# RTI-Dome-wire.net
KiCad netlist of a schematic drawn in EAGLE
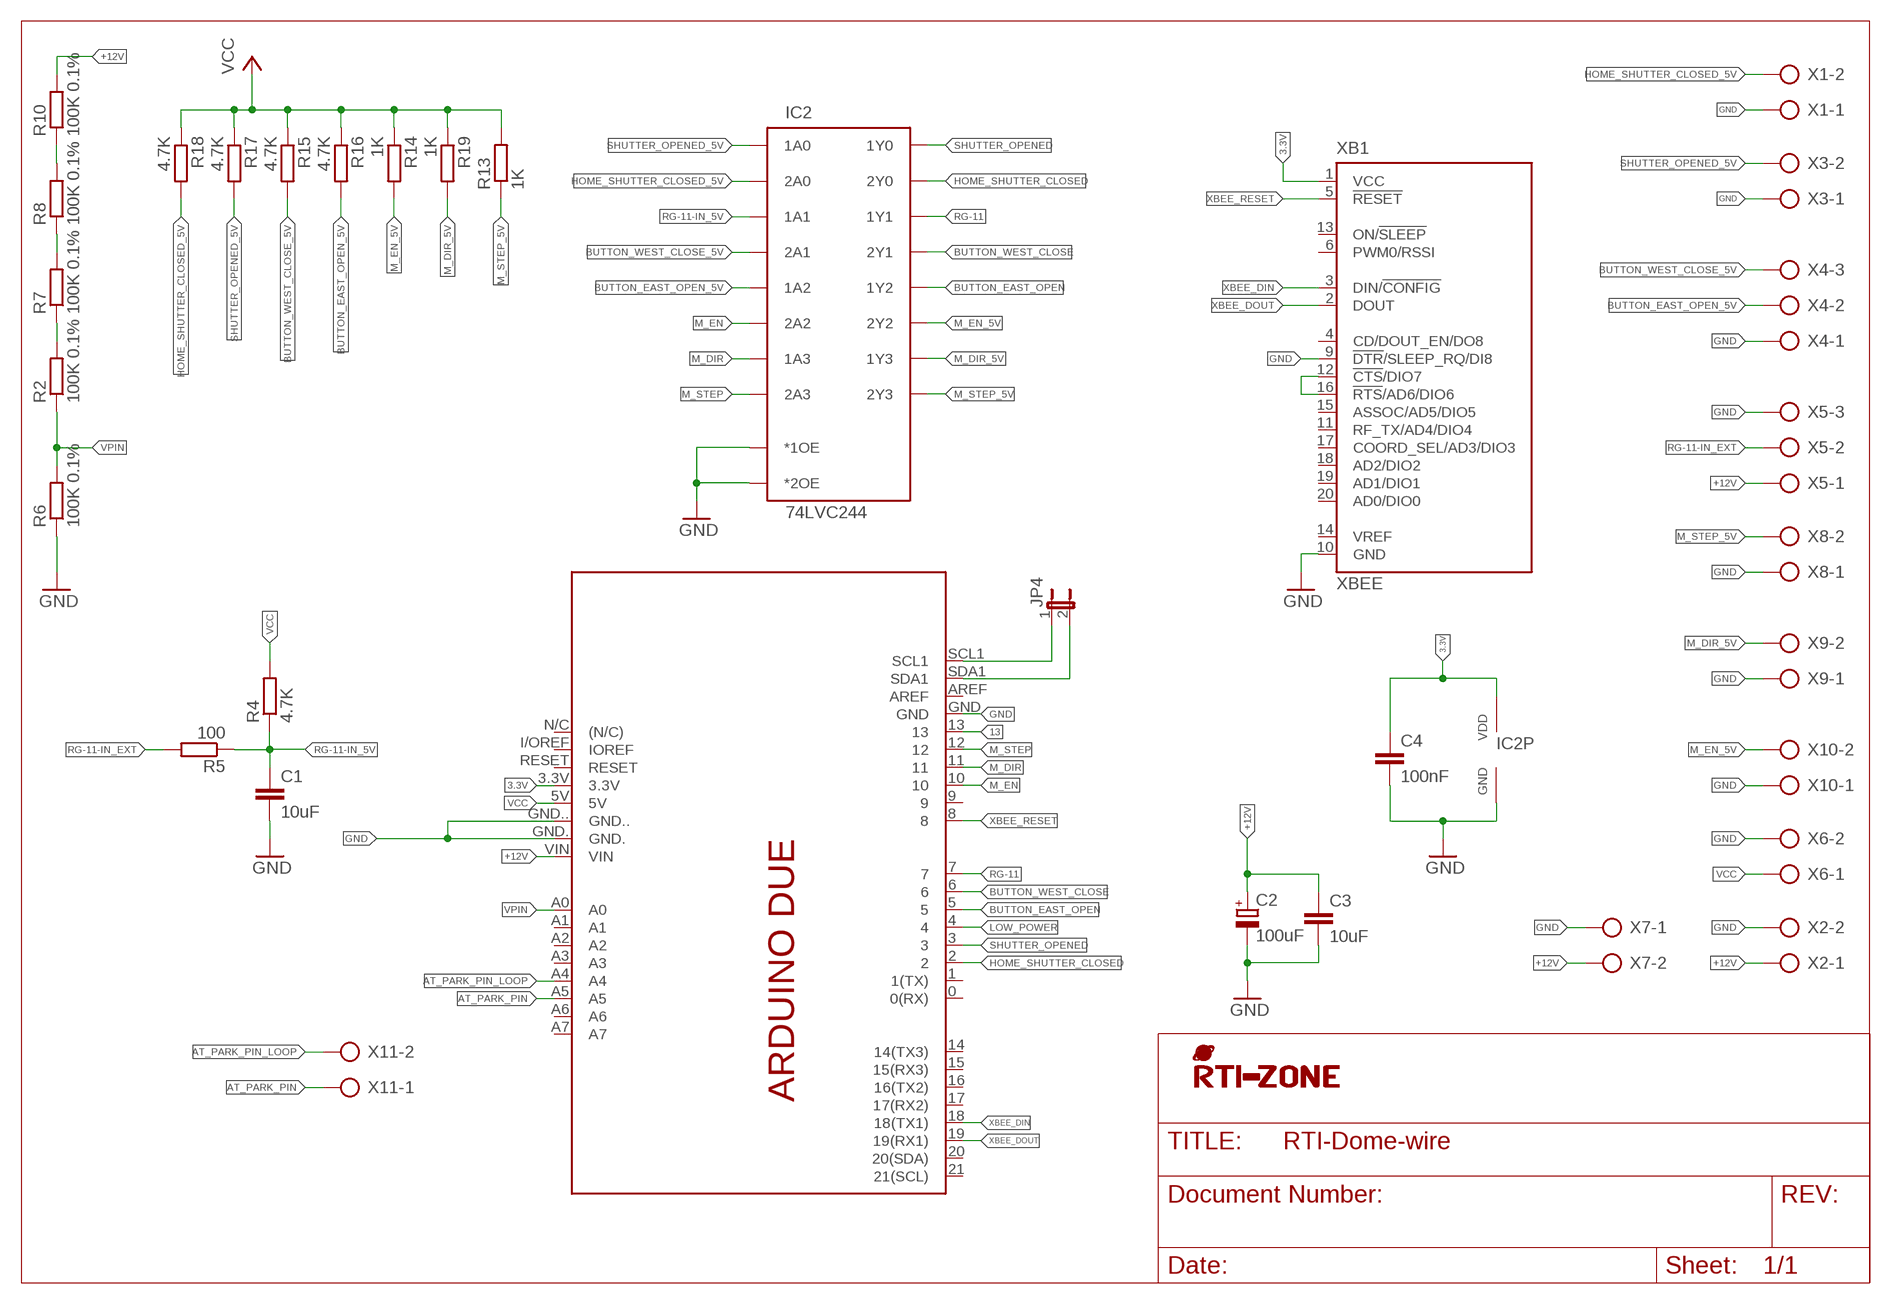
[diagram p0: schematic, sheet 1]

(export (version "E")
  (design (tool "Eeschema 10.0.6"))
  (components
    (comp (ref "C1")
      (value "10uF")
      (footprint "eagle-import:C0805")
      (libsource (lib "eagle-import") (part "C-EU'0805'"))
    )
    (comp (ref "C2")
      (value "100uF")
      (footprint "eagle-import:UD-10X10_NICHICON")
      (libsource (lib "eagle-import") (part "CPOL-EU"))
    )
    (comp (ref "C3")
      (value "10uF")
      (footprint "eagle-import:C0805")
      (libsource (lib "eagle-import") (part "C-EU'0805'"))
    )
    (comp (ref "C4")
      (value "100nF")
      (footprint "eagle-import:C0805")
      (libsource (lib "eagle-import") (part "C-EU'0805'"))
    )
    (comp (ref "IC2")
      (value "74LVC244")
      (footprint "eagle-import:TSSOP20")
      (libsource (lib "eagle-import") (part "74244LVC"))
    )
    (comp (ref "JP4")
      (value "JP1E")
      (footprint "eagle-import:JP1")
      (libsource (lib "eagle-import") (part "JP1E"))
    )
    (comp (ref "PCB1")
      (value "ARDUINO_DUE_SHIELD_SHORT")
      (footprint "eagle-import:ARDUINO_DUE_SHIELD_SHORT")
      (libsource (lib "eagle-import") (part "ARDUINO_DUE_SHIELD_SHORT"))
    )
    (comp (ref "R2")
      (value "100K 0.1%")
      (footprint "eagle-import:R0805")
      (libsource (lib "eagle-import") (part "R-EU'0805'"))
    )
    (comp (ref "R4")
      (value "4.7K")
      (footprint "eagle-import:R0805")
      (libsource (lib "eagle-import") (part "R-EU'0805'"))
    )
    (comp (ref "R5")
      (value "100")
      (footprint "eagle-import:R0805")
      (libsource (lib "eagle-import") (part "R-EU'0805'"))
    )
    (comp (ref "R6")
      (value "100K 0.1%")
      (footprint "eagle-import:R0805")
      (libsource (lib "eagle-import") (part "R-EU'0805'"))
    )
    (comp (ref "R7")
      (value "100K 0.1%")
      (footprint "eagle-import:R0805")
      (libsource (lib "eagle-import") (part "R-EU'0805'"))
    )
    (comp (ref "R8")
      (value "100K 0.1%")
      (footprint "eagle-import:R0805")
      (libsource (lib "eagle-import") (part "R-EU'0805'"))
    )
    (comp (ref "R10")
      (value "100K 0.1%")
      (footprint "eagle-import:R0805")
      (libsource (lib "eagle-import") (part "R-EU'0805'"))
    )
    (comp (ref "R13")
      (value "1K")
      (footprint "eagle-import:R0805")
      (libsource (lib "eagle-import") (part "R-EU'0805'"))
    )
    (comp (ref "R14")
      (value "1K")
      (footprint "eagle-import:R0805")
      (libsource (lib "eagle-import") (part "R-EU'0805'"))
    )
    (comp (ref "R15")
      (value "4.7K")
      (footprint "eagle-import:R0805")
      (libsource (lib "eagle-import") (part "R-EU'0805'"))
    )
    (comp (ref "R16")
      (value "4.7K")
      (footprint "eagle-import:R0805")
      (libsource (lib "eagle-import") (part "R-EU'0805'"))
    )
    (comp (ref "R17")
      (value "4.7K")
      (footprint "eagle-import:R0805")
      (libsource (lib "eagle-import") (part "R-EU'0805'"))
    )
    (comp (ref "R18")
      (value "4.7K")
      (footprint "eagle-import:R0805")
      (libsource (lib "eagle-import") (part "R-EU'0805'"))
    )
    (comp (ref "R19")
      (value "1K")
      (footprint "eagle-import:R0805")
      (libsource (lib "eagle-import") (part "R-EU'0805'"))
    )
    (comp (ref "U$4")
      (value "RTI-LOGO_BIG")
      (footprint "eagle-import:LOGO_BIG")
      (libsource (lib "eagle-import") (part "RTI-LOGO_BIG"))
    )
    (comp (ref "X1")
      (value "AK500/2")
      (footprint "eagle-import:AK500_2")
      (libsource (lib "eagle-import") (part "AK500/2"))
    )
    (comp (ref "X2")
      (value "AK500/2")
      (footprint "eagle-import:AK500_2")
      (libsource (lib "eagle-import") (part "AK500/2"))
    )
    (comp (ref "X3")
      (value "AK500/2")
      (footprint "eagle-import:AK500_2")
      (libsource (lib "eagle-import") (part "AK500/2"))
    )
    (comp (ref "X4")
      (value "AK500/3")
      (footprint "eagle-import:AK500_3")
      (libsource (lib "eagle-import") (part "AK500/3"))
    )
    (comp (ref "X5")
      (value "AK500/3")
      (footprint "eagle-import:AK500_3")
      (libsource (lib "eagle-import") (part "AK500/3"))
    )
    (comp (ref "X6")
      (value "AK500/2")
      (footprint "eagle-import:AK500_2")
      (libsource (lib "eagle-import") (part "AK500/2"))
    )
    (comp (ref "X7")
      (value "AK500/2")
      (footprint "eagle-import:AK500_2")
      (libsource (lib "eagle-import") (part "AK500/2"))
    )
    (comp (ref "X8")
      (value "AK500/2")
      (footprint "eagle-import:AK500_2")
      (libsource (lib "eagle-import") (part "AK500/2"))
    )
    (comp (ref "X9")
      (value "AK500/2")
      (footprint "eagle-import:AK500_2")
      (libsource (lib "eagle-import") (part "AK500/2"))
    )
    (comp (ref "X10")
      (value "AK500/2")
      (footprint "eagle-import:AK500_2")
      (libsource (lib "eagle-import") (part "AK500/2"))
    )
    (comp (ref "X11")
      (value "AK500/2")
      (footprint "eagle-import:AK500_2")
      (libsource (lib "eagle-import") (part "AK500/2"))
    )
    (comp (ref "XB1")
      (value "XBEE")
      (footprint "eagle-import:XBEE")
      (fields (field (name "MPN") "XBP24-Z7UIT-004"))
      (libsource (lib "eagle-import") (part "XBEE"))
    )
  )
  (nets
    (net (code "1") (name "+12V") (class "Default")
      (node (ref "C2") (pin "+") (pinfunction "+_+") (pintype "passive"))
      (node (ref "C3") (pin "1") (pinfunction "1_1") (pintype "passive"))
      (node (ref "PCB1") (pin "VIN") (pinfunction "VIN_VIN") (pintype "bidirectional"))
      (node (ref "R10") (pin "2") (pinfunction "2_2") (pintype "passive"))
      (node (ref "X2") (pin "1") (pinfunction "KL_1") (pintype "passive"))
      (node (ref "X5") (pin "1") (pinfunction "KL_1") (pintype "passive"))
      (node (ref "X7") (pin "2") (pinfunction "KL_2") (pintype "passive"))
    )
    (net (code "2") (name "3.3V") (class "Default")
      (node (ref "C4") (pin "1") (pinfunction "1_1") (pintype "passive"))
      (node (ref "IC2") (pin "P$20") (pinfunction "VDD_P$20") (pintype "power_in"))
      (node (ref "PCB1") (pin "3.3V") (pinfunction "3.3V_3.3V") (pintype "bidirectional"))
      (node (ref "XB1") (pin "1") (pinfunction "VCC_1") (pintype "power_in"))
    )
    (net (code "3") (name "13") (class "Default")
      (node (ref "PCB1") (pin "13") (pinfunction "13_13") (pintype "bidirectional"))
    )
    (net (code "4") (name "AT_PARK_PIN") (class "Default")
      (node (ref "PCB1") (pin "A5") (pinfunction "A5_A5") (pintype "bidirectional"))
      (node (ref "X11") (pin "1") (pinfunction "KL_1") (pintype "passive"))
    )
    (net (code "5") (name "AT_PARK_PIN_LOOP") (class "Default")
      (node (ref "PCB1") (pin "A4") (pinfunction "A4_A4") (pintype "bidirectional"))
      (node (ref "X11") (pin "2") (pinfunction "KL_2") (pintype "passive"))
    )
    (net (code "6") (name "BUTTON_EAST_OPEN") (class "Default")
      (node (ref "IC2") (pin "P$14") (pinfunction "1Y2_P$14") (pintype "output"))
      (node (ref "PCB1") (pin "5") (pinfunction "5_5") (pintype "bidirectional"))
    )
    (net (code "7") (name "BUTTON_EAST_OPEN_5V") (class "Default")
      (node (ref "IC2") (pin "P$6") (pinfunction "1A2_P$6") (pintype "input"))
      (node (ref "R16") (pin "2") (pinfunction "2_2") (pintype "passive"))
      (node (ref "X4") (pin "2") (pinfunction "KL_2") (pintype "passive"))
    )
    (net (code "8") (name "BUTTON_WEST_CLOSE") (class "Default")
      (node (ref "IC2") (pin "P$5") (pinfunction "2Y1_P$5") (pintype "output"))
      (node (ref "PCB1") (pin "6") (pinfunction "6_6") (pintype "bidirectional"))
    )
    (net (code "9") (name "BUTTON_WEST_CLOSE_5V") (class "Default")
      (node (ref "IC2") (pin "P$15") (pinfunction "2A1_P$15") (pintype "input"))
      (node (ref "R15") (pin "2") (pinfunction "2_2") (pintype "passive"))
      (node (ref "X4") (pin "3") (pinfunction "KL_3") (pintype "passive"))
    )
    (net (code "10") (name "GND") (class "Default")
      (node (ref "C1") (pin "2") (pinfunction "2_2") (pintype "passive"))
      (node (ref "C2") (pin "-") (pinfunction "-_-") (pintype "passive"))
      (node (ref "C3") (pin "2") (pinfunction "2_2") (pintype "passive"))
      (node (ref "C4") (pin "2") (pinfunction "2_2") (pintype "passive"))
      (node (ref "IC2") (pin "P$1") (pinfunction "*1OE_P$1") (pintype "input"))
      (node (ref "IC2") (pin "P$10") (pinfunction "GND_P$10") (pintype "power_in"))
      (node (ref "IC2") (pin "P$19") (pinfunction "*2OE_P$19") (pintype "input"))
      (node (ref "PCB1") (pin "GND") (pinfunction "GND_GND") (pintype "bidirectional"))
      (node (ref "PCB1") (pin "GND.") (pinfunction "GND._GND.") (pintype "bidirectional"))
      (node (ref "PCB1") (pin "GND..") (pinfunction "GND.._GND..") (pintype "bidirectional"))
      (node (ref "R6") (pin "1") (pinfunction "1_1") (pintype "passive"))
      (node (ref "X1") (pin "1") (pinfunction "KL_1") (pintype "passive"))
      (node (ref "X10") (pin "1") (pinfunction "KL_1") (pintype "passive"))
      (node (ref "X2") (pin "2") (pinfunction "KL_2") (pintype "passive"))
      (node (ref "X3") (pin "1") (pinfunction "KL_1") (pintype "passive"))
      (node (ref "X4") (pin "1") (pinfunction "KL_1") (pintype "passive"))
      (node (ref "X5") (pin "3") (pinfunction "KL_3") (pintype "passive"))
      (node (ref "X6") (pin "2") (pinfunction "KL_2") (pintype "passive"))
      (node (ref "X7") (pin "1") (pinfunction "KL_1") (pintype "passive"))
      (node (ref "X8") (pin "1") (pinfunction "KL_1") (pintype "passive"))
      (node (ref "X9") (pin "1") (pinfunction "KL_1") (pintype "passive"))
      (node (ref "XB1") (pin "10") (pinfunction "GND_10") (pintype "power_in"))
      (node (ref "XB1") (pin "9") (pinfunction "~{DTR}/SLEEP_RQ/DI8_9") (pintype "bidirectional"))
    )
    (net (code "11") (name "HOME_SHUTTER_CLOSED") (class "Default")
      (node (ref "IC2") (pin "P$3") (pinfunction "2Y0_P$3") (pintype "output"))
      (node (ref "PCB1") (pin "2") (pinfunction "2_2") (pintype "bidirectional"))
    )
    (net (code "12") (name "HOME_SHUTTER_CLOSED_5V") (class "Default")
      (node (ref "IC2") (pin "P$17") (pinfunction "2A0_P$17") (pintype "input"))
      (node (ref "R18") (pin "2") (pinfunction "2_2") (pintype "passive"))
      (node (ref "X1") (pin "2") (pinfunction "KL_2") (pintype "passive"))
    )
    (net (code "13") (name "LOW_POWER") (class "Default")
      (node (ref "PCB1") (pin "4") (pinfunction "4_4") (pintype "bidirectional"))
    )
    (net (code "14") (name "M_DIR") (class "Default")
      (node (ref "IC2") (pin "P$8") (pinfunction "1A3_P$8") (pintype "input"))
      (node (ref "PCB1") (pin "11") (pinfunction "11_11") (pintype "bidirectional"))
    )
    (net (code "15") (name "M_DIR_5V") (class "Default")
      (node (ref "IC2") (pin "P$12") (pinfunction "1Y3_P$12") (pintype "output"))
      (node (ref "R19") (pin "2") (pinfunction "2_2") (pintype "passive"))
      (node (ref "X9") (pin "2") (pinfunction "KL_2") (pintype "passive"))
    )
    (net (code "16") (name "M_EN") (class "Default")
      (node (ref "IC2") (pin "P$13") (pinfunction "2A2_P$13") (pintype "input"))
      (node (ref "PCB1") (pin "10") (pinfunction "10_10") (pintype "bidirectional"))
    )
    (net (code "17") (name "M_EN_5V") (class "Default")
      (node (ref "IC2") (pin "P$7") (pinfunction "2Y2_P$7") (pintype "output"))
      (node (ref "R14") (pin "2") (pinfunction "2_2") (pintype "passive"))
      (node (ref "X10") (pin "2") (pinfunction "KL_2") (pintype "passive"))
    )
    (net (code "18") (name "M_STEP") (class "Default")
      (node (ref "IC2") (pin "P$11") (pinfunction "2A3_P$11") (pintype "input"))
      (node (ref "PCB1") (pin "12") (pinfunction "12_12") (pintype "bidirectional"))
    )
    (net (code "19") (name "M_STEP_5V") (class "Default")
      (node (ref "IC2") (pin "P$9") (pinfunction "2Y3_P$9") (pintype "output"))
      (node (ref "R13") (pin "1") (pinfunction "1_1") (pintype "passive"))
      (node (ref "X8") (pin "2") (pinfunction "KL_2") (pintype "passive"))
    )
    (net (code "20") (name "Net-(JP4-Pad1)") (class "Default")
      (node (ref "JP4") (pin "1") (pinfunction "1_1") (pintype "passive"))
      (node (ref "PCB1") (pin "SCL1") (pinfunction "SCL1_SCL1") (pintype "bidirectional"))
    )
    (net (code "21") (name "Net-(JP4-Pad2)") (class "Default")
      (node (ref "JP4") (pin "2") (pinfunction "2_2") (pintype "passive"))
      (node (ref "PCB1") (pin "SDA1") (pinfunction "SDA1_SDA1") (pintype "bidirectional"))
    )
    (net (code "22") (name "Net-(R2-Pad2)") (class "Default")
      (node (ref "R2") (pin "2") (pinfunction "2_2") (pintype "passive"))
      (node (ref "R7") (pin "1") (pinfunction "1_1") (pintype "passive"))
    )
    (net (code "23") (name "Net-(R7-Pad2)") (class "Default")
      (node (ref "R7") (pin "2") (pinfunction "2_2") (pintype "passive"))
      (node (ref "R8") (pin "1") (pinfunction "1_1") (pintype "passive"))
    )
    (net (code "24") (name "Net-(R10-Pad1)") (class "Default")
      (node (ref "R10") (pin "1") (pinfunction "1_1") (pintype "passive"))
      (node (ref "R8") (pin "2") (pinfunction "2_2") (pintype "passive"))
    )
    (net (code "25") (name "Net-(XB1-~{CTS}{slash}DIO7)") (class "Default")
      (node (ref "XB1") (pin "12") (pinfunction "~{CTS}/DIO7_12") (pintype "bidirectional"))
      (node (ref "XB1") (pin "16") (pinfunction "~{RTS}/AD6/DIO6_16") (pintype "bidirectional"))
    )
    (net (code "26") (name "RG-11") (class "Default")
      (node (ref "IC2") (pin "P$16") (pinfunction "1Y1_P$16") (pintype "output"))
      (node (ref "PCB1") (pin "7") (pinfunction "7_7") (pintype "bidirectional"))
    )
    (net (code "27") (name "RG-11-IN_5V") (class "Default")
      (node (ref "C1") (pin "1") (pinfunction "1_1") (pintype "passive"))
      (node (ref "IC2") (pin "P$4") (pinfunction "1A1_P$4") (pintype "input"))
      (node (ref "R4") (pin "1") (pinfunction "1_1") (pintype "passive"))
      (node (ref "R5") (pin "1") (pinfunction "1_1") (pintype "passive"))
    )
    (net (code "28") (name "RG-11-IN_EXT") (class "Default")
      (node (ref "R5") (pin "2") (pinfunction "2_2") (pintype "passive"))
      (node (ref "X5") (pin "2") (pinfunction "KL_2") (pintype "passive"))
    )
    (net (code "29") (name "SHUTTER_OPENED") (class "Default")
      (node (ref "IC2") (pin "P$18") (pinfunction "1Y0_P$18") (pintype "output"))
      (node (ref "PCB1") (pin "3") (pinfunction "3_3") (pintype "bidirectional"))
    )
    (net (code "30") (name "SHUTTER_OPENED_5V") (class "Default")
      (node (ref "IC2") (pin "P$2") (pinfunction "1A0_P$2") (pintype "input"))
      (node (ref "R17") (pin "2") (pinfunction "2_2") (pintype "passive"))
      (node (ref "X3") (pin "2") (pinfunction "KL_2") (pintype "passive"))
    )
    (net (code "31") (name "VCC") (class "Default")
      (node (ref "PCB1") (pin "5V") (pinfunction "5V_5V") (pintype "bidirectional"))
      (node (ref "R13") (pin "2") (pinfunction "2_2") (pintype "passive"))
      (node (ref "R14") (pin "1") (pinfunction "1_1") (pintype "passive"))
      (node (ref "R15") (pin "1") (pinfunction "1_1") (pintype "passive"))
      (node (ref "R16") (pin "1") (pinfunction "1_1") (pintype "passive"))
      (node (ref "R17") (pin "1") (pinfunction "1_1") (pintype "passive"))
      (node (ref "R18") (pin "1") (pinfunction "1_1") (pintype "passive"))
      (node (ref "R19") (pin "1") (pinfunction "1_1") (pintype "passive"))
      (node (ref "R4") (pin "2") (pinfunction "2_2") (pintype "passive"))
      (node (ref "X6") (pin "1") (pinfunction "KL_1") (pintype "passive"))
    )
    (net (code "32") (name "VPIN") (class "Default")
      (node (ref "PCB1") (pin "A0") (pinfunction "A0_A0") (pintype "bidirectional"))
      (node (ref "R2") (pin "1") (pinfunction "1_1") (pintype "passive"))
      (node (ref "R6") (pin "2") (pinfunction "2_2") (pintype "passive"))
    )
    (net (code "33") (name "XBEE_DIN") (class "Default")
      (node (ref "PCB1") (pin "18") (pinfunction "18(TX1)_18") (pintype "bidirectional"))
      (node (ref "XB1") (pin "3") (pinfunction "DIN/~{CONFIG}_3") (pintype "input"))
    )
    (net (code "34") (name "XBEE_DOUT") (class "Default")
      (node (ref "PCB1") (pin "19") (pinfunction "19(RX1)_19") (pintype "bidirectional"))
      (node (ref "XB1") (pin "2") (pinfunction "DOUT_2") (pintype "output"))
    )
    (net (code "35") (name "XBEE_RESET") (class "Default")
      (node (ref "PCB1") (pin "8") (pinfunction "8_8") (pintype "bidirectional"))
      (node (ref "XB1") (pin "5") (pinfunction "~{RESET}_5") (pintype "input"))
    )
    (net (code "36") (name "unconnected-(PCB1-(N{slash}C)-PadN{slash}C)") (class "Default")
      (node (ref "PCB1") (pin "N/C") (pinfunction "(N/C)_N/C") (pintype "bidirectional"))
    )
    (net (code "37") (name "unconnected-(PCB1-0(RX)-Pad0)") (class "Default")
      (node (ref "PCB1") (pin "0") (pinfunction "0(RX)_0") (pintype "bidirectional"))
    )
    (net (code "38") (name "unconnected-(PCB1-1(TX)-Pad1)") (class "Default")
      (node (ref "PCB1") (pin "1") (pinfunction "1(TX)_1") (pintype "bidirectional"))
    )
    (net (code "39") (name "unconnected-(PCB1-14(TX3)-Pad14)") (class "Default")
      (node (ref "PCB1") (pin "14") (pinfunction "14(TX3)_14") (pintype "bidirectional"))
    )
    (net (code "40") (name "unconnected-(PCB1-15(RX3)-Pad15)") (class "Default")
      (node (ref "PCB1") (pin "15") (pinfunction "15(RX3)_15") (pintype "bidirectional"))
    )
    (net (code "41") (name "unconnected-(PCB1-16(TX2)-Pad16)") (class "Default")
      (node (ref "PCB1") (pin "16") (pinfunction "16(TX2)_16") (pintype "bidirectional"))
    )
    (net (code "42") (name "unconnected-(PCB1-17(RX2)-Pad17)") (class "Default")
      (node (ref "PCB1") (pin "17") (pinfunction "17(RX2)_17") (pintype "bidirectional"))
    )
    (net (code "43") (name "unconnected-(PCB1-20(SDA)-Pad20)") (class "Default")
      (node (ref "PCB1") (pin "20") (pinfunction "20(SDA)_20") (pintype "bidirectional"))
    )
    (net (code "44") (name "unconnected-(PCB1-21(SCL)-Pad21)") (class "Default")
      (node (ref "PCB1") (pin "21") (pinfunction "21(SCL)_21") (pintype "bidirectional"))
    )
    (net (code "45") (name "unconnected-(PCB1-IOREF-PadI{slash}OREF)") (class "Default")
      (node (ref "PCB1") (pin "I/OREF") (pinfunction "IOREF_I/OREF") (pintype "bidirectional"))
    )
    (net (code "46") (name "unconnected-(PCB1-Pad9)") (class "Default")
      (node (ref "PCB1") (pin "9") (pinfunction "9_9") (pintype "bidirectional"))
    )
    (net (code "47") (name "unconnected-(PCB1-PadA1)") (class "Default")
      (node (ref "PCB1") (pin "A1") (pinfunction "A1_A1") (pintype "bidirectional"))
    )
    (net (code "48") (name "unconnected-(PCB1-PadA2)") (class "Default")
      (node (ref "PCB1") (pin "A2") (pinfunction "A2_A2") (pintype "bidirectional"))
    )
    (net (code "49") (name "unconnected-(PCB1-PadA3)") (class "Default")
      (node (ref "PCB1") (pin "A3") (pinfunction "A3_A3") (pintype "bidirectional"))
    )
    (net (code "50") (name "unconnected-(PCB1-PadA6)") (class "Default")
      (node (ref "PCB1") (pin "A6") (pinfunction "A6_A6") (pintype "bidirectional"))
    )
    (net (code "51") (name "unconnected-(PCB1-PadA7)") (class "Default")
      (node (ref "PCB1") (pin "A7") (pinfunction "A7_A7") (pintype "bidirectional"))
    )
    (net (code "52") (name "unconnected-(PCB1-PadAREF)") (class "Default")
      (node (ref "PCB1") (pin "AREF") (pinfunction "AREF_AREF") (pintype "bidirectional"))
    )
    (net (code "53") (name "unconnected-(PCB1-PadRESET)") (class "Default")
      (node (ref "PCB1") (pin "RESET") (pinfunction "RESET_RESET") (pintype "bidirectional"))
    )
    (net (code "54") (name "unconnected-(XB1-AD0{slash}DIO0-Pad20)") (class "Default")
      (node (ref "XB1") (pin "20") (pinfunction "AD0/DIO0_20") (pintype "bidirectional"))
    )
    (net (code "55") (name "unconnected-(XB1-AD1{slash}DIO1-Pad19)") (class "Default")
      (node (ref "XB1") (pin "19") (pinfunction "AD1/DIO1_19") (pintype "bidirectional"))
    )
    (net (code "56") (name "unconnected-(XB1-AD2{slash}DIO2-Pad18)") (class "Default")
      (node (ref "XB1") (pin "18") (pinfunction "AD2/DIO2_18") (pintype "bidirectional"))
    )
    (net (code "57") (name "unconnected-(XB1-ASSOC{slash}AD5{slash}DIO5-Pad15)") (class "Default")
      (node (ref "XB1") (pin "15") (pinfunction "ASSOC/AD5/DIO5_15") (pintype "bidirectional"))
    )
    (net (code "58") (name "unconnected-(XB1-CD{slash}DOUT_EN{slash}DO8-Pad4)") (class "Default")
      (node (ref "XB1") (pin "4") (pinfunction "CD/DOUT_EN/DO8_4") (pintype "output"))
    )
    (net (code "59") (name "unconnected-(XB1-COORD_SEL{slash}AD3{slash}DIO3-Pad17)") (class "Default")
      (node (ref "XB1") (pin "17") (pinfunction "COORD_SEL/AD3/DIO3_17") (pintype "bidirectional"))
    )
    (net (code "60") (name "unconnected-(XB1-ON{slash}~{SLEEP}-Pad13)") (class "Default")
      (node (ref "XB1") (pin "13") (pinfunction "ON/~{SLEEP}_13") (pintype "output"))
    )
    (net (code "61") (name "unconnected-(XB1-PWM0{slash}RSSI-Pad6)") (class "Default")
      (node (ref "XB1") (pin "6") (pinfunction "PWM0/RSSI_6") (pintype "output"))
    )
    (net (code "62") (name "unconnected-(XB1-RF_TX{slash}AD4{slash}DIO4-Pad11)") (class "Default")
      (node (ref "XB1") (pin "11") (pinfunction "RF_TX/AD4/DIO4_11") (pintype "bidirectional"))
    )
    (net (code "63") (name "unconnected-(XB1-VREF-Pad14)") (class "Default")
      (node (ref "XB1") (pin "14") (pinfunction "VREF_14") (pintype "input"))
    )
  )
)
